# RaspberryPi-breakout.net
KiCad netlist of a schematic drawn in EAGLE
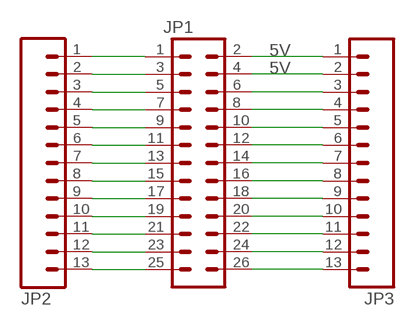
[diagram p0: schematic, sheet 1]

(export (version "E")
  (design (tool "Eeschema 10.0.6"))
  (components
    (comp (ref "JP1")
      (value "M13X22X13")
      (footprint "eagle-import:2X13")
      (libsource (lib "eagle-import") (part "M13X22X13"))
    )
    (comp (ref "JP2")
      (value "M13")
      (footprint "eagle-import:1X13")
      (libsource (lib "eagle-import") (part "M13"))
    )
    (comp (ref "JP3")
      (value "M13")
      (footprint "eagle-import:1X13")
      (libsource (lib "eagle-import") (part "M13"))
    )
  )
  (nets
    (net (code "1") (name "Net-(JP1-Pad1)") (class "Default")
      (node (ref "JP1") (pin "1") (pinfunction "1_1") (pintype "passive"))
      (node (ref "JP2") (pin "1") (pinfunction "1_1") (pintype "passive"))
    )
    (net (code "2") (name "Net-(JP1-Pad2)") (class "Default")
      (node (ref "JP1") (pin "2") (pinfunction "2_2") (pintype "passive"))
      (node (ref "JP3") (pin "1") (pinfunction "1_1") (pintype "passive"))
    )
    (net (code "3") (name "Net-(JP1-Pad3)") (class "Default")
      (node (ref "JP1") (pin "3") (pinfunction "3_3") (pintype "passive"))
      (node (ref "JP2") (pin "2") (pinfunction "2_2") (pintype "passive"))
    )
    (net (code "4") (name "Net-(JP1-Pad4)") (class "Default")
      (node (ref "JP1") (pin "4") (pinfunction "4_4") (pintype "passive"))
      (node (ref "JP3") (pin "2") (pinfunction "2_2") (pintype "passive"))
    )
    (net (code "5") (name "Net-(JP1-Pad5)") (class "Default")
      (node (ref "JP1") (pin "5") (pinfunction "5_5") (pintype "passive"))
      (node (ref "JP2") (pin "3") (pinfunction "3_3") (pintype "passive"))
    )
    (net (code "6") (name "Net-(JP1-Pad6)") (class "Default")
      (node (ref "JP1") (pin "6") (pinfunction "6_6") (pintype "passive"))
      (node (ref "JP3") (pin "3") (pinfunction "3_3") (pintype "passive"))
    )
    (net (code "7") (name "Net-(JP1-Pad7)") (class "Default")
      (node (ref "JP1") (pin "7") (pinfunction "7_7") (pintype "passive"))
      (node (ref "JP2") (pin "4") (pinfunction "4_4") (pintype "passive"))
    )
    (net (code "8") (name "Net-(JP1-Pad8)") (class "Default")
      (node (ref "JP1") (pin "8") (pinfunction "8_8") (pintype "passive"))
      (node (ref "JP3") (pin "4") (pinfunction "4_4") (pintype "passive"))
    )
    (net (code "9") (name "Net-(JP1-Pad9)") (class "Default")
      (node (ref "JP1") (pin "9") (pinfunction "9_9") (pintype "passive"))
      (node (ref "JP2") (pin "5") (pinfunction "5_5") (pintype "passive"))
    )
    (net (code "10") (name "Net-(JP1-Pad10)") (class "Default")
      (node (ref "JP1") (pin "10") (pinfunction "10_10") (pintype "passive"))
      (node (ref "JP3") (pin "5") (pinfunction "5_5") (pintype "passive"))
    )
    (net (code "11") (name "Net-(JP1-Pad11)") (class "Default")
      (node (ref "JP1") (pin "11") (pinfunction "11_11") (pintype "passive"))
      (node (ref "JP2") (pin "6") (pinfunction "6_6") (pintype "passive"))
    )
    (net (code "12") (name "Net-(JP1-Pad12)") (class "Default")
      (node (ref "JP1") (pin "12") (pinfunction "12_12") (pintype "passive"))
      (node (ref "JP3") (pin "6") (pinfunction "6_6") (pintype "passive"))
    )
    (net (code "13") (name "Net-(JP1-Pad13)") (class "Default")
      (node (ref "JP1") (pin "13") (pinfunction "13_13") (pintype "passive"))
      (node (ref "JP2") (pin "7") (pinfunction "7_7") (pintype "passive"))
    )
    (net (code "14") (name "Net-(JP1-Pad14)") (class "Default")
      (node (ref "JP1") (pin "14") (pinfunction "14_14") (pintype "passive"))
      (node (ref "JP3") (pin "7") (pinfunction "7_7") (pintype "passive"))
    )
    (net (code "15") (name "Net-(JP1-Pad15)") (class "Default")
      (node (ref "JP1") (pin "15") (pinfunction "15_15") (pintype "passive"))
      (node (ref "JP2") (pin "8") (pinfunction "8_8") (pintype "passive"))
    )
    (net (code "16") (name "Net-(JP1-Pad16)") (class "Default")
      (node (ref "JP1") (pin "16") (pinfunction "16_16") (pintype "passive"))
      (node (ref "JP3") (pin "8") (pinfunction "8_8") (pintype "passive"))
    )
    (net (code "17") (name "Net-(JP1-Pad17)") (class "Default")
      (node (ref "JP1") (pin "17") (pinfunction "17_17") (pintype "passive"))
      (node (ref "JP2") (pin "9") (pinfunction "9_9") (pintype "passive"))
    )
    (net (code "18") (name "Net-(JP1-Pad18)") (class "Default")
      (node (ref "JP1") (pin "18") (pinfunction "18_18") (pintype "passive"))
      (node (ref "JP3") (pin "9") (pinfunction "9_9") (pintype "passive"))
    )
    (net (code "19") (name "Net-(JP1-Pad19)") (class "Default")
      (node (ref "JP1") (pin "19") (pinfunction "19_19") (pintype "passive"))
      (node (ref "JP2") (pin "10") (pinfunction "10_10") (pintype "passive"))
    )
    (net (code "20") (name "Net-(JP1-Pad20)") (class "Default")
      (node (ref "JP1") (pin "20") (pinfunction "20_20") (pintype "passive"))
      (node (ref "JP3") (pin "10") (pinfunction "10_10") (pintype "passive"))
    )
    (net (code "21") (name "Net-(JP1-Pad21)") (class "Default")
      (node (ref "JP1") (pin "21") (pinfunction "21_21") (pintype "passive"))
      (node (ref "JP2") (pin "11") (pinfunction "11_11") (pintype "passive"))
    )
    (net (code "22") (name "Net-(JP1-Pad22)") (class "Default")
      (node (ref "JP1") (pin "22") (pinfunction "22_22") (pintype "passive"))
      (node (ref "JP3") (pin "11") (pinfunction "11_11") (pintype "passive"))
    )
    (net (code "23") (name "Net-(JP1-Pad23)") (class "Default")
      (node (ref "JP1") (pin "23") (pinfunction "23_23") (pintype "passive"))
      (node (ref "JP2") (pin "12") (pinfunction "12_12") (pintype "passive"))
    )
    (net (code "24") (name "Net-(JP1-Pad24)") (class "Default")
      (node (ref "JP1") (pin "24") (pinfunction "24_24") (pintype "passive"))
      (node (ref "JP3") (pin "12") (pinfunction "12_12") (pintype "passive"))
    )
    (net (code "25") (name "Net-(JP1-Pad25)") (class "Default")
      (node (ref "JP1") (pin "25") (pinfunction "25_25") (pintype "passive"))
      (node (ref "JP2") (pin "13") (pinfunction "13_13") (pintype "passive"))
    )
    (net (code "26") (name "Net-(JP1-Pad26)") (class "Default")
      (node (ref "JP1") (pin "26") (pinfunction "26_26") (pintype "passive"))
      (node (ref "JP3") (pin "13") (pinfunction "13_13") (pintype "passive"))
    )
  )
)
